# EasyEDA_Pro_Project_-_01.net
KiCad netlist of a schematic drawn in EasyEDA Pro
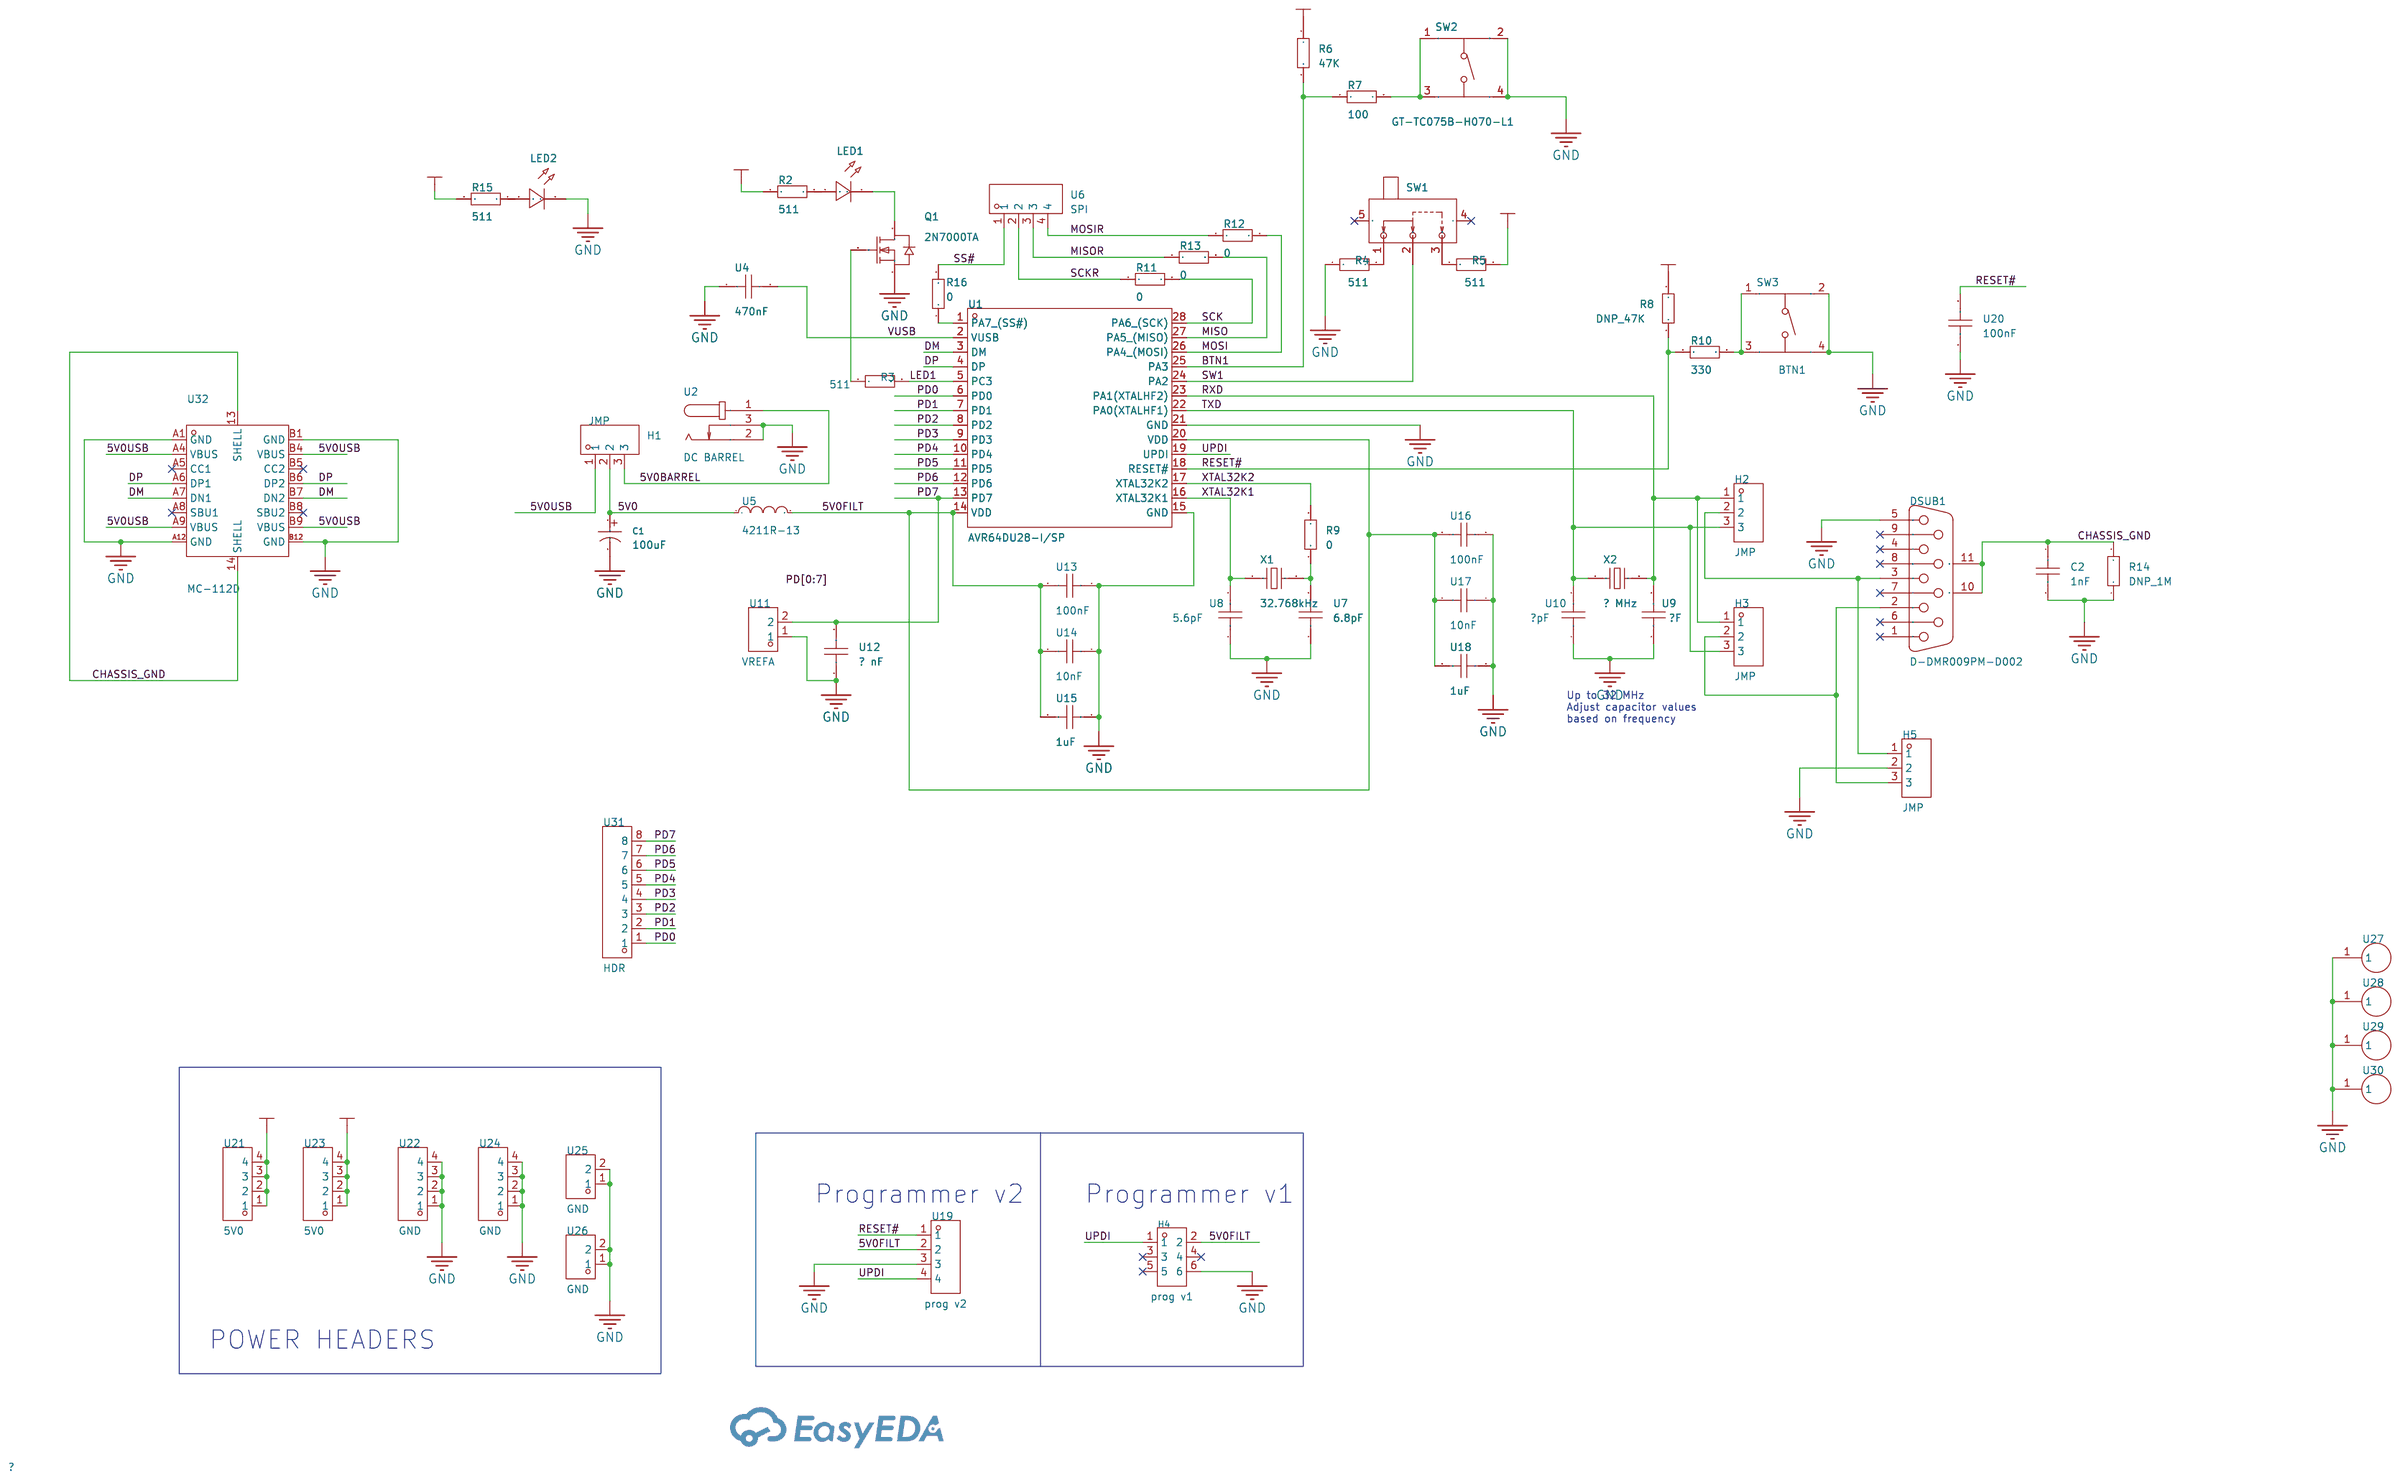
[diagram p0: schematic sheet]

(export (version "E")
  (design (tool "Eeschema 10.0.6"))
  (components
    (comp (ref "C1")
      (value "100uF")
      (footprint "easyedapro:CAP-TH_BD5.0-P2.00-D0.8-FD")
      (fields
        (field (name "Manufacturer Part") "KS107M010D07RR0VH2FP0")
        (field (name "Manufacturer") "CX(承兴)")
      )
      (libsource (lib "easyedapro") (part "100uF 10V 5*7"))
    )
    (comp (ref "C2")
      (value "1nF")
      (footprint "easyedapro:CAP-TH_L6.0-W3.5-P7.50-D1.0")
      (fields (field (name "Manufacturer Part") "Y25E1E102M") (field (name "Manufacturer") "HEL(鸿志)"))
      (libsource (lib "easyedapro") (part "Y25E1E102M"))
    )
    (comp (ref "DSUB1")
      (value "D-DMR009PM-D002")
      (footprint "easyedapro:DSUB-TH_DMR-9P")
      (fields (field (name "Manufacturer") "Ckmtw(灿科盟)"))
      (libsource (lib "easyedapro") (part "DMR-9P"))
    )
    (comp (ref "H1")
      (value "JMP")
      (footprint "easyedapro:HDR-TH_3P-P2.54-V-M-1")
      (fields (field (name "Manufacturer") "JILN(锦凌)"))
      (libsource (lib "easyedapro") (part "12251103CNG0S115001"))
    )
    (comp (ref "H2")
      (value "JMP")
      (footprint "easyedapro:HDR-TH_3P-P2.54-V-M-1")
      (fields (field (name "Manufacturer") "JILN(锦凌)"))
      (libsource (lib "easyedapro") (part "12251103CNG0S115001"))
    )
    (comp (ref "H3")
      (value "JMP")
      (footprint "easyedapro:HDR-TH_3P-P2.54-V-M-1")
      (fields (field (name "Manufacturer") "JILN(锦凌)"))
      (libsource (lib "easyedapro") (part "12251103CNG0S115001"))
    )
    (comp (ref "H4")
      (value "prog v1")
      (footprint "easyedapro:HDR-TH_6P-P2.54-V-M-R2-C3-S2.54")
      (fields (field (name "Manufacturer") "Liansheng(连盛)"))
      (libsource (lib "easyedapro") (part "PH-01291"))
    )
    (comp (ref "H5")
      (value "JMP")
      (footprint "easyedapro:HDR-TH_3P-P2.54-V-M-1")
      (fields (field (name "Manufacturer") "JILN(锦凌)"))
      (libsource (lib "easyedapro") (part "12251103CNG0S115001"))
    )
    (comp (ref "LED1")
      (value "~")
      (footprint "easyedapro:LED-TH_BD3.0-P2.54-FD")
      (libsource (lib "easyedapro") (part "LED_TH-R"))
    )
    (comp (ref "LED2")
      (value "~")
      (footprint "easyedapro:LED-TH_BD3.0-P2.54-FD")
      (libsource (lib "easyedapro") (part "LED_TH-R"))
    )
    (comp (ref "Q1")
      (value "2N7000TA")
      (footprint "easyedapro:TO-92-3_L4.8-W3.7-P2.54-L")
      (fields (field (name "Manufacturer") "onsemi(安森美)"))
      (libsource (lib "easyedapro") (part "2N7000TA"))
    )
    (comp (ref "R2")
      (value "511")
      (footprint "easyedapro:RES-TH_BD1.8-L3.2-P7.20-D0.4")
      (libsource (lib "easyedapro") (part "Res"))
    )
    (comp (ref "R3")
      (value "511")
      (footprint "easyedapro:RES-TH_BD1.8-L3.2-P7.20-D0.4")
      (libsource (lib "easyedapro") (part "Res"))
    )
    (comp (ref "R4")
      (value "511")
      (footprint "easyedapro:RES-TH_BD1.8-L3.2-P7.20-D0.4")
      (libsource (lib "easyedapro") (part "Res"))
    )
    (comp (ref "R5")
      (value "511")
      (footprint "easyedapro:RES-TH_BD1.8-L3.2-P7.20-D0.4")
      (libsource (lib "easyedapro") (part "Res"))
    )
    (comp (ref "R6")
      (value "47K")
      (footprint "easyedapro:RES-TH_BD1.8-L3.2-P7.20-D0.4")
      (libsource (lib "easyedapro") (part "Res"))
    )
    (comp (ref "R7")
      (value "100")
      (footprint "easyedapro:RES-TH_BD1.8-L3.2-P7.20-D0.4")
      (libsource (lib "easyedapro") (part "Res"))
    )
    (comp (ref "R8")
      (value "DNP_47K")
      (footprint "easyedapro:RES-TH_BD1.8-L3.2-P7.20-D0.4")
      (libsource (lib "easyedapro") (part "Res"))
    )
    (comp (ref "R9")
      (value "0")
      (footprint "easyedapro:RES-TH_BD1.8-L3.2-P7.20-D0.4")
      (libsource (lib "easyedapro") (part "Res"))
    )
    (comp (ref "R10")
      (value "330")
      (footprint "easyedapro:RES-TH_BD1.8-L3.2-P7.20-D0.4")
      (libsource (lib "easyedapro") (part "Res"))
    )
    (comp (ref "R11")
      (value "0")
      (footprint "easyedapro:RES-TH_BD1.8-L3.2-P7.20-D0.4")
      (libsource (lib "easyedapro") (part "Res"))
    )
    (comp (ref "R12")
      (value "0")
      (footprint "easyedapro:RES-TH_BD1.8-L3.2-P7.20-D0.4")
      (libsource (lib "easyedapro") (part "Res"))
    )
    (comp (ref "R13")
      (value "0")
      (footprint "easyedapro:RES-TH_BD1.8-L3.2-P7.20-D0.4")
      (libsource (lib "easyedapro") (part "Res"))
    )
    (comp (ref "R14")
      (value "DNP_1M")
      (footprint "easyedapro:RES-TH_BD1.8-L3.2-P7.20-D0.4")
      (libsource (lib "easyedapro") (part "Res"))
    )
    (comp (ref "R15")
      (value "511")
      (footprint "easyedapro:RES-TH_BD1.8-L3.2-P7.20-D0.4")
      (libsource (lib "easyedapro") (part "Res"))
    )
    (comp (ref "R16")
      (value "0")
      (footprint "easyedapro:RES-TH_BD1.8-L3.2-P7.20-D0.4")
      (libsource (lib "easyedapro") (part "Res"))
    )
    (comp (ref "SW1")
      (value "SS-12D07G4")
      (footprint "easyedapro:SW-TH_DEALON_SS-12D02-VGX")
      (fields (field (name "Manufacturer") "HanElectricity(瀚源)"))
      (libsource (lib "easyedapro") (part "SS-12D07G4"))
    )
    (comp (ref "SW2")
      (value "GT-TC075B-H070-L1")
      (footprint "easyedapro:KEY-TH_4P-L4.5-W4.5-P3.00-LS5.8")
      (fields (field (name "Manufacturer") "G-Switch(品赞)"))
      (libsource (lib "easyedapro") (part "GT-TC075B-H070-L1"))
    )
    (comp (ref "SW3")
      (value "BTN1")
      (footprint "easyedapro:KEY-TH_4P-L4.5-W4.5-P3.00-LS5.8")
      (fields (field (name "Manufacturer") "G-Switch(品赞)"))
      (libsource (lib "easyedapro") (part "GT-TC075B-H070-L1"))
    )
    (comp (ref "U1")
      (value "AVR64DU28-I/SP")
      (footprint "easyedapro:SPDIP-28_L34.7-W7.2-P2.54-LS7.9-BL")
      (fields (field (name "Manufacturer") "MICROCHIP(美国微芯)"))
      (libsource (lib "easyedapro") (part "AVR64DB28-I/SP"))
    )
    (comp (ref "U2")
      (value "DC BARREL")
      (footprint "easyedapro:DC-IN-TH_DC-005-2.0_C22459640")
      (fields (field (name "Manufacturer") "HanElectricity(瀚源)"))
      (libsource (lib "easyedapro") (part "DC-005-2.0_C22459640"))
    )
    (comp (ref "U4")
      (value "470nF")
      (footprint "easyedapro:CAP-TH_L4.8-W2.4-P5.08-D0.6")
      (fields (field (name "Manufacturer Part") "178MU0009") (field (name "Manufacturer") "KNSCHA(科尼盛)"))
      (libsource (lib "easyedapro") (part "178MU0009"))
    )
    (comp (ref "U5")
      (value "4211R-13")
      (footprint "easyedapro:IND-TH_BD3.5-L4.4_4211R-13")
      (description "Impedance @ Frequency:50Ω@100MHz Circuits:1")
      (fields (field (name "Manufacturer") "API Delevan"))
      (libsource (lib "easyedapro") (part "4211R-13"))
    )
    (comp (ref "U6")
      (value "SPI")
      (footprint "easyedapro:HDR-TH_4P-P2.00-V-M")
      (fields (field (name "Manufacturer") "Yxcon(宇熙精密)"))
      (libsource (lib "easyedapro") (part "P220-1104A0BS087A1"))
    )
    (comp (ref "U7")
      (value "6.8pF")
      (footprint "easyedapro:CAP-TH_L4.8-W2.4-P5.08-D0.6")
      (fields (field (name "Manufacturer Part") "178MU0009") (field (name "Manufacturer") "KNSCHA(科尼盛)"))
      (libsource (lib "easyedapro") (part "178MU0009"))
    )
    (comp (ref "U8")
      (value "5.6pF")
      (footprint "easyedapro:CAP-TH_L4.8-W2.4-P5.08-D0.6")
      (fields (field (name "Manufacturer Part") "178MU0009") (field (name "Manufacturer") "KNSCHA(科尼盛)"))
      (libsource (lib "easyedapro") (part "178MU0009"))
    )
    (comp (ref "U9")
      (value "?F")
      (footprint "easyedapro:CAP-TH_L4.8-W2.4-P5.08-D0.6")
      (fields (field (name "Manufacturer Part") "178MU0009") (field (name "Manufacturer") "KNSCHA(科尼盛)"))
      (libsource (lib "easyedapro") (part "178MU0009"))
    )
    (comp (ref "U10")
      (value "?pF")
      (footprint "easyedapro:CAP-TH_L4.8-W2.4-P5.08-D0.6")
      (fields (field (name "Manufacturer Part") "178MU0009") (field (name "Manufacturer") "KNSCHA(科尼盛)"))
      (libsource (lib "easyedapro") (part "178MU0009"))
    )
    (comp (ref "U11")
      (value "VREFA")
      (footprint "easyedapro:HDR-TH_2P-P2.00-V-M")
      (fields (field (name "Manufacturer") "hanxia(韩下)"))
      (libsource (lib "easyedapro") (part "HX PZ2.0-1X2P ZZ"))
    )
    (comp (ref "U12")
      (value "? nF")
      (footprint "easyedapro:CAP-TH_L4.8-W2.4-P5.08-D0.6")
      (fields (field (name "Manufacturer Part") "178MU0009") (field (name "Manufacturer") "KNSCHA(科尼盛)"))
      (libsource (lib "easyedapro") (part "178MU0009"))
    )
    (comp (ref "U13")
      (value "100nF")
      (footprint "easyedapro:CAP-TH_L4.8-W2.4-P5.08-D0.6")
      (fields (field (name "Manufacturer Part") "178MU0009") (field (name "Manufacturer") "KNSCHA(科尼盛)"))
      (libsource (lib "easyedapro") (part "178MU0009"))
    )
    (comp (ref "U14")
      (value "10nF")
      (footprint "easyedapro:CAP-TH_L4.8-W2.4-P5.08-D0.6")
      (fields (field (name "Manufacturer Part") "178MU0009") (field (name "Manufacturer") "KNSCHA(科尼盛)"))
      (libsource (lib "easyedapro") (part "178MU0009"))
    )
    (comp (ref "U15")
      (value "1uF")
      (footprint "easyedapro:CAP-TH_L4.8-W2.4-P5.08-D0.6")
      (fields (field (name "Manufacturer Part") "178MU0009") (field (name "Manufacturer") "KNSCHA(科尼盛)"))
      (libsource (lib "easyedapro") (part "178MU0009"))
    )
    (comp (ref "U16")
      (value "100nF")
      (footprint "easyedapro:CAP-TH_L4.8-W2.4-P5.08-D0.6")
      (fields (field (name "Manufacturer Part") "178MU0009") (field (name "Manufacturer") "KNSCHA(科尼盛)"))
      (libsource (lib "easyedapro") (part "178MU0009"))
    )
    (comp (ref "U17")
      (value "10nF")
      (footprint "easyedapro:CAP-TH_L4.8-W2.4-P5.08-D0.6")
      (fields (field (name "Manufacturer Part") "178MU0009") (field (name "Manufacturer") "KNSCHA(科尼盛)"))
      (libsource (lib "easyedapro") (part "178MU0009"))
    )
    (comp (ref "U18")
      (value "1uF")
      (footprint "easyedapro:CAP-TH_L4.8-W2.4-P5.08-D0.6")
      (fields (field (name "Manufacturer Part") "178MU0009") (field (name "Manufacturer") "KNSCHA(科尼盛)"))
      (libsource (lib "easyedapro") (part "178MU0009"))
    )
    (comp (ref "U19")
      (value "prog v2")
      (footprint "easyedapro:HDR-TH_4P-P2.00-V-M")
      (fields (field (name "Manufacturer") "Yxcon(宇熙精密)"))
      (libsource (lib "easyedapro") (part "P220-1104A0BS087A1"))
    )
    (comp (ref "U20")
      (value "100nF")
      (footprint "easyedapro:CAP-TH_L4.8-W2.4-P5.08-D0.6")
      (fields (field (name "Manufacturer Part") "178MU0009") (field (name "Manufacturer") "KNSCHA(科尼盛)"))
      (libsource (lib "easyedapro") (part "178MU0009"))
    )
    (comp (ref "U21")
      (value "5V0")
      (footprint "easyedapro:HDR-TH_4P-P2.00-V-M")
      (fields (field (name "Manufacturer") "Yxcon(宇熙精密)"))
      (libsource (lib "easyedapro") (part "P220-1104A0BS087A1"))
    )
    (comp (ref "U22")
      (value "GND")
      (footprint "easyedapro:HDR-TH_4P-P2.00-V-M")
      (fields (field (name "Manufacturer") "Yxcon(宇熙精密)"))
      (libsource (lib "easyedapro") (part "P220-1104A0BS087A1"))
    )
    (comp (ref "U23")
      (value "5V0")
      (footprint "easyedapro:HDR-TH_4P-P2.00-V-M")
      (fields (field (name "Manufacturer") "Yxcon(宇熙精密)"))
      (libsource (lib "easyedapro") (part "P220-1104A0BS087A1"))
    )
    (comp (ref "U24")
      (value "GND")
      (footprint "easyedapro:HDR-TH_4P-P2.00-V-M")
      (fields (field (name "Manufacturer") "Yxcon(宇熙精密)"))
      (libsource (lib "easyedapro") (part "P220-1104A0BS087A1"))
    )
    (comp (ref "U25")
      (value "GND")
      (footprint "easyedapro:HDR-TH_2P-P2.00-V-M")
      (fields (field (name "Manufacturer") "hanxia(韩下)"))
      (libsource (lib "easyedapro") (part "HX PZ2.0-1X2P ZZ"))
    )
    (comp (ref "U26")
      (value "GND")
      (footprint "easyedapro:HDR-TH_2P-P2.00-V-M")
      (fields (field (name "Manufacturer") "hanxia(韩下)"))
      (libsource (lib "easyedapro") (part "HX PZ2.0-1X2P ZZ"))
    )
    (comp (ref "U27")
      (value "~")
      (footprint "easyedapro:Standoff 2.0mm")
      (libsource (lib "easyedapro") (part "Standoff 2.0mm"))
    )
    (comp (ref "U28")
      (value "~")
      (footprint "easyedapro:Standoff 2.0mm")
      (libsource (lib "easyedapro") (part "Standoff 2.0mm"))
    )
    (comp (ref "U29")
      (value "~")
      (footprint "easyedapro:Standoff 2.0mm")
      (libsource (lib "easyedapro") (part "Standoff 2.0mm"))
    )
    (comp (ref "U30")
      (value "~")
      (footprint "easyedapro:Standoff 2.0mm")
      (libsource (lib "easyedapro") (part "Standoff 2.0mm"))
    )
    (comp (ref "U31")
      (value "HDR")
      (footprint "easyedapro:HDR-TH_8P-P2.54-V-M")
      (fields (field (name "Manufacturer") "HANBO(汉博)"))
      (libsource (lib "easyedapro") (part "HB-PH3-25418PB2GOP"))
    )
    (comp (ref "U32")
      (value "MC-112D")
      (footprint "easyedapro:USB-C-TH_HANBO_MC-112D")
      (fields (field (name "Manufacturer") "HANBO(汉博)"))
      (libsource (lib "easyedapro") (part "MC-112D"))
    )
    (comp (ref "X1")
      (value "32.768kHz")
      (footprint "easyedapro:OSC-TH_BD2.0-P0.70-D0.3")
      (fields
        (field (name "Manufacturer Part") "TAXD32768K2BGBBZT2S")
        (field (name "Manufacturer") "YJX(雅晶鑫)")
      )
      (libsource (lib "easyedapro") (part "TAXD32768K2BGBBZT2S"))
    )
    (comp (ref "X2")
      (value "? MHz")
      (footprint "easyedapro:OSC-TH_BD2.0-P0.70-D0.3")
      (fields
        (field (name "Manufacturer Part") "TAXD32768K2BGBBZT2S")
        (field (name "Manufacturer") "YJX(雅晶鑫)")
      )
      (libsource (lib "easyedapro") (part "TAXD32768K2BGBBZT2S"))
    )
  )
  (nets
    (net (code "1") (name "/5V0BARREL") (class "Default")
      (node (ref "H1") (pin "3") (pinfunction "3_3") (pintype "unspecified"))
      (node (ref "U2") (pin "1") (pinfunction "1_1") (pintype "unspecified"))
    )
    (net (code "2") (name "/5V0FILT") (class "Default")
      (node (ref "H4") (pin "2") (pinfunction "2_2") (pintype "input"))
      (node (ref "U1") (pin "14") (pinfunction "VDD_14") (pintype "unspecified"))
      (node (ref "U1") (pin "20") (pinfunction "VDD_20") (pintype "unspecified"))
      (node (ref "U13") (pin "2") (pinfunction "2_2") (pintype "unspecified"))
      (node (ref "U14") (pin "2") (pinfunction "2_2") (pintype "unspecified"))
      (node (ref "U15") (pin "2") (pinfunction "2_2") (pintype "unspecified"))
      (node (ref "U16") (pin "2") (pinfunction "2_2") (pintype "unspecified"))
      (node (ref "U17") (pin "2") (pinfunction "2_2") (pintype "unspecified"))
      (node (ref "U18") (pin "2") (pinfunction "2_2") (pintype "unspecified"))
      (node (ref "U19") (pin "2") (pinfunction "2_2") (pintype "unspecified"))
      (node (ref "U5") (pin "2") (pinfunction "2_2") (pintype "unspecified"))
    )
    (net (code "3") (name "/5V0USB") (class "Default")
      (node (ref "H1") (pin "1") (pinfunction "1_1") (pintype "unspecified"))
      (node (ref "U32") (pin "A4") (pinfunction "VBUS_A4") (pintype "unspecified"))
      (node (ref "U32") (pin "A9") (pinfunction "VBUS_A9") (pintype "unspecified"))
      (node (ref "U32") (pin "B4") (pinfunction "VBUS_B4") (pintype "unspecified"))
      (node (ref "U32") (pin "B9") (pinfunction "VBUS_B9") (pintype "unspecified"))
    )
    (net (code "4") (name "/BTN1") (class "Default")
      (node (ref "R6") (pin "2") (pinfunction "2_2") (pintype "input"))
      (node (ref "R7") (pin "1") (pinfunction "1_1") (pintype "input"))
      (node (ref "U1") (pin "25") (pinfunction "PA3_25") (pintype "unspecified"))
    )
    (net (code "5") (name "/CHASSIS_GND") (class "Default")
      (node (ref "C2") (pin "1") (pinfunction "1_1") (pintype "input"))
      (node (ref "DSUB1") (pin "10") (pinfunction "MH1_10") (pintype "input"))
      (node (ref "DSUB1") (pin "11") (pinfunction "MH2_11") (pintype "input"))
      (node (ref "R14") (pin "2") (pinfunction "2_2") (pintype "input"))
      (node (ref "U32") (pin "13") (pinfunction "SHELL_13") (pintype "unspecified"))
      (node (ref "U32") (pin "14") (pinfunction "SHELL_14") (pintype "unspecified"))
    )
    (net (code "6") (name "/DM") (class "Default")
      (node (ref "U1") (pin "3") (pinfunction "DM_3") (pintype "unspecified"))
      (node (ref "U32") (pin "A7") (pinfunction "DN1_A7") (pintype "unspecified"))
      (node (ref "U32") (pin "B7") (pinfunction "DN2_B7") (pintype "unspecified"))
    )
    (net (code "7") (name "/DP") (class "Default")
      (node (ref "U1") (pin "4") (pinfunction "DP_4") (pintype "unspecified"))
      (node (ref "U32") (pin "A6") (pinfunction "DP1_A6") (pintype "unspecified"))
      (node (ref "U32") (pin "B6") (pinfunction "DP2_B6") (pintype "unspecified"))
    )
    (net (code "8") (name "/LED1") (class "Default")
      (node (ref "R3") (pin "2") (pinfunction "2_2") (pintype "input"))
      (node (ref "U1") (pin "5") (pinfunction "PC3_5") (pintype "unspecified"))
    )
    (net (code "9") (name "/MISO") (class "Default")
      (node (ref "R13") (pin "2") (pinfunction "2_2") (pintype "input"))
      (node (ref "U1") (pin "27") (pinfunction "PA5_(MISO)_27") (pintype "unspecified"))
    )
    (net (code "10") (name "/MISOR") (class "Default")
      (node (ref "R13") (pin "1") (pinfunction "1_1") (pintype "input"))
      (node (ref "U6") (pin "3") (pinfunction "3_3") (pintype "unspecified"))
    )
    (net (code "11") (name "/MOSI") (class "Default")
      (node (ref "R12") (pin "2") (pinfunction "2_2") (pintype "input"))
      (node (ref "U1") (pin "26") (pinfunction "PA4_(MOSI)_26") (pintype "unspecified"))
    )
    (net (code "12") (name "/MOSIR") (class "Default")
      (node (ref "R12") (pin "1") (pinfunction "1_1") (pintype "input"))
      (node (ref "U6") (pin "4") (pinfunction "4_4") (pintype "unspecified"))
    )
    (net (code "13") (name "/PD0") (class "Default")
      (node (ref "U1") (pin "6") (pinfunction "PD0_6") (pintype "unspecified"))
      (node (ref "U31") (pin "1") (pinfunction "1_1") (pintype "unspecified"))
    )
    (net (code "14") (name "/PD1") (class "Default")
      (node (ref "U1") (pin "7") (pinfunction "PD1_7") (pintype "unspecified"))
      (node (ref "U31") (pin "2") (pinfunction "2_2") (pintype "unspecified"))
    )
    (net (code "15") (name "/PD2") (class "Default")
      (node (ref "U1") (pin "8") (pinfunction "PD2_8") (pintype "unspecified"))
      (node (ref "U31") (pin "3") (pinfunction "3_3") (pintype "unspecified"))
    )
    (net (code "16") (name "/PD3") (class "Default")
      (node (ref "U1") (pin "9") (pinfunction "PD3_9") (pintype "unspecified"))
      (node (ref "U31") (pin "4") (pinfunction "4_4") (pintype "unspecified"))
    )
    (net (code "17") (name "/PD4") (class "Default")
      (node (ref "U1") (pin "10") (pinfunction "PD4_10") (pintype "unspecified"))
      (node (ref "U31") (pin "5") (pinfunction "5_5") (pintype "unspecified"))
    )
    (net (code "18") (name "/PD5") (class "Default")
      (node (ref "U1") (pin "11") (pinfunction "PD5_11") (pintype "unspecified"))
      (node (ref "U31") (pin "6") (pinfunction "6_6") (pintype "unspecified"))
    )
    (net (code "19") (name "/PD6") (class "Default")
      (node (ref "U1") (pin "12") (pinfunction "PD6_12") (pintype "unspecified"))
      (node (ref "U31") (pin "7") (pinfunction "7_7") (pintype "unspecified"))
    )
    (net (code "20") (name "/PD7") (class "Default")
      (node (ref "U1") (pin "13") (pinfunction "PD7_13") (pintype "unspecified"))
      (node (ref "U11") (pin "2") (pinfunction "2_2") (pintype "unspecified"))
      (node (ref "U12") (pin "2") (pinfunction "2_2") (pintype "unspecified"))
      (node (ref "U31") (pin "8") (pinfunction "8_8") (pintype "unspecified"))
    )
    (net (code "22") (name "/RESET#") (class "Default")
      (node (ref "R10") (pin "1") (pinfunction "1_1") (pintype "input"))
      (node (ref "R8") (pin "2") (pinfunction "2_2") (pintype "input"))
      (node (ref "U1") (pin "18") (pinfunction "RESET#_18") (pintype "unspecified"))
      (node (ref "U19") (pin "1") (pinfunction "1_1") (pintype "unspecified"))
      (node (ref "U20") (pin "2") (pinfunction "2_2") (pintype "unspecified"))
    )
    (net (code "23") (name "/RXD") (class "Default")
      (node (ref "H2") (pin "1") (pinfunction "1_1") (pintype "unspecified"))
      (node (ref "H3") (pin "1") (pinfunction "1_1") (pintype "unspecified"))
      (node (ref "U1") (pin "23") (pinfunction "PA1(XTALHF2)_23") (pintype "unspecified"))
      (node (ref "U9") (pin "2") (pinfunction "2_2") (pintype "unspecified"))
      (node (ref "X2") (pin "2") (pinfunction "2_2") (pintype "input"))
    )
    (net (code "24") (name "/SCK") (class "Default")
      (node (ref "R11") (pin "2") (pinfunction "2_2") (pintype "input"))
      (node (ref "U1") (pin "28") (pinfunction "PA6_(SCK)_28") (pintype "unspecified"))
    )
    (net (code "25") (name "/SCKR") (class "Default")
      (node (ref "R11") (pin "1") (pinfunction "1_1") (pintype "input"))
      (node (ref "U6") (pin "2") (pinfunction "2_2") (pintype "unspecified"))
    )
    (net (code "26") (name "/SS#") (class "Default")
      (node (ref "R16") (pin "2") (pinfunction "2_2") (pintype "input"))
      (node (ref "U6") (pin "1") (pinfunction "1_1") (pintype "unspecified"))
    )
    (net (code "27") (name "/SW1") (class "Default")
      (node (ref "SW1") (pin "2") (pinfunction "2_2") (pintype "unspecified"))
      (node (ref "U1") (pin "24") (pinfunction "PA2_24") (pintype "unspecified"))
    )
    (net (code "28") (name "/TXD") (class "Default")
      (node (ref "H2") (pin "3") (pinfunction "3_3") (pintype "unspecified"))
      (node (ref "H3") (pin "3") (pinfunction "3_3") (pintype "unspecified"))
      (node (ref "U1") (pin "22") (pinfunction "PA0(XTALHF1)_22") (pintype "unspecified"))
      (node (ref "U10") (pin "2") (pinfunction "2_2") (pintype "unspecified"))
      (node (ref "X2") (pin "1") (pinfunction "1_1") (pintype "input"))
    )
    (net (code "29") (name "/UPDI") (class "Default")
      (node (ref "H4") (pin "1") (pinfunction "1_1") (pintype "input"))
      (node (ref "U1") (pin "19") (pinfunction "UPDI_19") (pintype "unspecified"))
      (node (ref "U19") (pin "4") (pinfunction "4_4") (pintype "unspecified"))
    )
    (net (code "30") (name "/VUSB") (class "Default")
      (node (ref "U1") (pin "2") (pinfunction "VUSB_2") (pintype "unspecified"))
      (node (ref "U4") (pin "2") (pinfunction "2_2") (pintype "unspecified"))
    )
    (net (code "31") (name "/XTAL32K1") (class "Default")
      (node (ref "U1") (pin "16") (pinfunction "XTAL32K1_16") (pintype "unspecified"))
      (node (ref "U8") (pin "2") (pinfunction "2_2") (pintype "unspecified"))
      (node (ref "X1") (pin "1") (pinfunction "1_1") (pintype "input"))
    )
    (net (code "32") (name "/XTAL32K2") (class "Default")
      (node (ref "R9") (pin "1") (pinfunction "1_1") (pintype "input"))
      (node (ref "U1") (pin "17") (pinfunction "XTAL32K2_17") (pintype "unspecified"))
    )
    (net (code "33") (name "5V0") (class "Default")
      (node (ref "C1") (pin "1") (pinfunction "1_1") (pintype "input"))
      (node (ref "H1") (pin "2") (pinfunction "2_2") (pintype "unspecified"))
      (node (ref "R15") (pin "2") (pinfunction "2_2") (pintype "input"))
      (node (ref "R2") (pin "2") (pinfunction "2_2") (pintype "input"))
      (node (ref "R5") (pin "2") (pinfunction "2_2") (pintype "input"))
      (node (ref "R6") (pin "1") (pinfunction "1_1") (pintype "input"))
      (node (ref "R8") (pin "1") (pinfunction "1_1") (pintype "input"))
      (node (ref "U21") (pin "1") (pinfunction "1_1") (pintype "unspecified"))
      (node (ref "U21") (pin "2") (pinfunction "2_2") (pintype "unspecified"))
      (node (ref "U21") (pin "3") (pinfunction "3_3") (pintype "unspecified"))
      (node (ref "U21") (pin "4") (pinfunction "4_4") (pintype "unspecified"))
      (node (ref "U23") (pin "1") (pinfunction "1_1") (pintype "unspecified"))
      (node (ref "U23") (pin "2") (pinfunction "2_2") (pintype "unspecified"))
      (node (ref "U23") (pin "3") (pinfunction "3_3") (pintype "unspecified"))
      (node (ref "U23") (pin "4") (pinfunction "4_4") (pintype "unspecified"))
      (node (ref "U5") (pin "1") (pinfunction "1_1") (pintype "unspecified"))
    )
    (net (code "34") (name "GND") (class "Default")
      (node (ref "C1") (pin "2") (pinfunction "2_2") (pintype "input"))
      (node (ref "C2") (pin "2") (pinfunction "2_2") (pintype "input"))
      (node (ref "DSUB1") (pin "5") (pinfunction "5_5") (pintype "input"))
      (node (ref "H4") (pin "6") (pinfunction "6_6") (pintype "input"))
      (node (ref "H5") (pin "2") (pinfunction "2_2") (pintype "unspecified"))
      (node (ref "LED2") (pin "2") (pinfunction "A_2") (pintype "input"))
      (node (ref "Q1") (pin "1") (pinfunction "S_1") (pintype "unspecified"))
      (node (ref "R14") (pin "1") (pinfunction "1_1") (pintype "input"))
      (node (ref "R4") (pin "1") (pinfunction "1_1") (pintype "input"))
      (node (ref "SW2") (pin "2") (pinfunction "2_2") (pintype "unspecified"))
      (node (ref "SW2") (pin "4") (pinfunction "4_4") (pintype "unspecified"))
      (node (ref "SW3") (pin "2") (pinfunction "2_2") (pintype "unspecified"))
      (node (ref "SW3") (pin "4") (pinfunction "4_4") (pintype "unspecified"))
      (node (ref "U1") (pin "15") (pinfunction "GND_15") (pintype "unspecified"))
      (node (ref "U1") (pin "21") (pinfunction "GND_21") (pintype "unspecified"))
      (node (ref "U10") (pin "1") (pinfunction "1_1") (pintype "unspecified"))
      (node (ref "U11") (pin "1") (pinfunction "1_1") (pintype "unspecified"))
      (node (ref "U12") (pin "1") (pinfunction "1_1") (pintype "unspecified"))
      (node (ref "U13") (pin "1") (pinfunction "1_1") (pintype "unspecified"))
      (node (ref "U14") (pin "1") (pinfunction "1_1") (pintype "unspecified"))
      (node (ref "U15") (pin "1") (pinfunction "1_1") (pintype "unspecified"))
      (node (ref "U16") (pin "1") (pinfunction "1_1") (pintype "unspecified"))
      (node (ref "U17") (pin "1") (pinfunction "1_1") (pintype "unspecified"))
      (node (ref "U18") (pin "1") (pinfunction "1_1") (pintype "unspecified"))
      (node (ref "U19") (pin "3") (pinfunction "3_3") (pintype "unspecified"))
      (node (ref "U2") (pin "2") (pinfunction "2_2") (pintype "unspecified"))
      (node (ref "U2") (pin "3") (pinfunction "3_3") (pintype "unspecified"))
      (node (ref "U20") (pin "1") (pinfunction "1_1") (pintype "unspecified"))
      (node (ref "U22") (pin "1") (pinfunction "1_1") (pintype "unspecified"))
      (node (ref "U22") (pin "2") (pinfunction "2_2") (pintype "unspecified"))
      (node (ref "U22") (pin "3") (pinfunction "3_3") (pintype "unspecified"))
      (node (ref "U22") (pin "4") (pinfunction "4_4") (pintype "unspecified"))
      (node (ref "U24") (pin "1") (pinfunction "1_1") (pintype "unspecified"))
      (node (ref "U24") (pin "2") (pinfunction "2_2") (pintype "unspecified"))
      (node (ref "U24") (pin "3") (pinfunction "3_3") (pintype "unspecified"))
      (node (ref "U24") (pin "4") (pinfunction "4_4") (pintype "unspecified"))
      (node (ref "U25") (pin "1") (pinfunction "1_1") (pintype "unspecified"))
      (node (ref "U25") (pin "2") (pinfunction "2_2") (pintype "unspecified"))
      (node (ref "U26") (pin "1") (pinfunction "1_1") (pintype "unspecified"))
      (node (ref "U26") (pin "2") (pinfunction "2_2") (pintype "unspecified"))
      (node (ref "U27") (pin "1") (pinfunction "1_1") (pintype "input"))
      (node (ref "U28") (pin "1") (pinfunction "1_1") (pintype "input"))
      (node (ref "U29") (pin "1") (pinfunction "1_1") (pintype "input"))
      (node (ref "U30") (pin "1") (pinfunction "1_1") (pintype "input"))
      (node (ref "U32") (pin "A1") (pinfunction "GND_A1") (pintype "unspecified"))
      (node (ref "U32") (pin "A12") (pinfunction "GND_A12") (pintype "unspecified"))
      (node (ref "U32") (pin "B1") (pinfunction "GND_B1") (pintype "unspecified"))
      (node (ref "U32") (pin "B12") (pinfunction "GND_B12") (pintype "unspecified"))
      (node (ref "U4") (pin "1") (pinfunction "1_1") (pintype "unspecified"))
      (node (ref "U7") (pin "1") (pinfunction "1_1") (pintype "unspecified"))
      (node (ref "U8") (pin "1") (pinfunction "1_1") (pintype "unspecified"))
      (node (ref "U9") (pin "1") (pinfunction "1_1") (pintype "unspecified"))
    )
    (net (code "35") (name "Net-(DSUB1-Pad2)") (class "Default")
      (node (ref "DSUB1") (pin "2") (pinfunction "2_2") (pintype "input"))
      (node (ref "H3") (pin "2") (pinfunction "2_2") (pintype "unspecified"))
      (node (ref "H5") (pin "3") (pinfunction "3_3") (pintype "unspecified"))
    )
    (net (code "36") (name "Net-(DSUB1-Pad3)") (class "Default")
      (node (ref "DSUB1") (pin "3") (pinfunction "3_3") (pintype "input"))
      (node (ref "H2") (pin "2") (pinfunction "2_2") (pintype "unspecified"))
      (node (ref "H5") (pin "1") (pinfunction "1_1") (pintype "unspecified"))
    )
    (net (code "37") (name "Net-(LED1-A)") (class "Default")
      (node (ref "LED1") (pin "2") (pinfunction "A_2") (pintype "input"))
      (node (ref "Q1") (pin "3") (pinfunction "D_3") (pintype "unspecified"))
    )
    (net (code "38") (name "Net-(LED1-C)") (class "Default")
      (node (ref "LED1") (pin "1") (pinfunction "C_1") (pintype "input"))
      (node (ref "R2") (pin "1") (pinfunction "1_1") (pintype "input"))
    )
    (net (code "39") (name "Net-(LED2-C)") (class "Default")
      (node (ref "LED2") (pin "1") (pinfunction "C_1") (pintype "input"))
      (node (ref "R15") (pin "1") (pinfunction "1_1") (pintype "input"))
    )
    (net (code "40") (name "Net-(Q1-G)") (class "Default")
      (node (ref "Q1") (pin "2") (pinfunction "G_2") (pintype "unspecified"))
      (node (ref "R3") (pin "1") (pinfunction "1_1") (pintype "input"))
    )
    (net (code "41") (name "Net-(R4-Pad2)") (class "Default")
      (node (ref "R4") (pin "2") (pinfunction "2_2") (pintype "input"))
      (node (ref "SW1") (pin "1") (pinfunction "1_1") (pintype "unspecified"))
    )
    (net (code "42") (name "Net-(R5-Pad1)") (class "Default")
      (node (ref "R5") (pin "1") (pinfunction "1_1") (pintype "input"))
      (node (ref "SW1") (pin "3") (pinfunction "3_3") (pintype "unspecified"))
    )
    (net (code "43") (name "Net-(R7-Pad2)") (class "Default")
      (node (ref "R7") (pin "2") (pinfunction "2_2") (pintype "input"))
      (node (ref "SW2") (pin "1") (pinfunction "1_1") (pintype "unspecified"))
      (node (ref "SW2") (pin "3") (pinfunction "3_3") (pintype "unspecified"))
    )
    (net (code "44") (name "Net-(R9-Pad2)") (class "Default")
      (node (ref "R9") (pin "2") (pinfunction "2_2") (pintype "input"))
      (node (ref "U7") (pin "2") (pinfunction "2_2") (pintype "unspecified"))
      (node (ref "X1") (pin "2") (pinfunction "2_2") (pintype "input"))
    )
    (net (code "45") (name "Net-(R10-Pad2)") (class "Default")
      (node (ref "R10") (pin "2") (pinfunction "2_2") (pintype "input"))
      (node (ref "SW3") (pin "1") (pinfunction "1_1") (pintype "unspecified"))
      (node (ref "SW3") (pin "3") (pinfunction "3_3") (pintype "unspecified"))
    )
    (net (code "46") (name "Net-(U1-PA7_(SS#))") (class "Default")
      (node (ref "R16") (pin "1") (pinfunction "1_1") (pintype "input"))
      (node (ref "U1") (pin "1") (pinfunction "PA7_(SS#)_1") (pintype "unspecified"))
    )
    (net (code "47") (name "unconnected-(DSUB1-Pad1)") (class "Default")
      (node (ref "DSUB1") (pin "1") (pinfunction "1_1") (pintype "input+no_connect"))
    )
    (net (code "48") (name "unconnected-(DSUB1-Pad4)") (class "Default")
      (node (ref "DSUB1") (pin "4") (pinfunction "4_4") (pintype "input+no_connect"))
    )
    (net (code "49") (name "unconnected-(DSUB1-Pad6)") (class "Default")
      (node (ref "DSUB1") (pin "6") (pinfunction "6_6") (pintype "input+no_connect"))
    )
    (net (code "50") (name "unconnected-(DSUB1-Pad7)") (class "Default")
      (node (ref "DSUB1") (pin "7") (pinfunction "7_7") (pintype "input+no_connect"))
    )
    (net (code "51") (name "unconnected-(DSUB1-Pad8)") (class "Default")
      (node (ref "DSUB1") (pin "8") (pinfunction "8_8") (pintype "input+no_connect"))
    )
    (net (code "52") (name "unconnected-(DSUB1-Pad9)") (class "Default")
      (node (ref "DSUB1") (pin "9") (pinfunction "9_9") (pintype "input+no_connect"))
    )
    (net (code "53") (name "unconnected-(H4-Pad3)") (class "Default")
      (node (ref "H4") (pin "3") (pinfunction "3_3") (pintype "input+no_connect"))
    )
    (net (code "54") (name "unconnected-(H4-Pad4)") (class "Default")
      (node (ref "H4") (pin "4") (pinfunction "4_4") (pintype "input+no_connect"))
    )
    (net (code "55") (name "unconnected-(H4-Pad5)") (class "Default")
      (node (ref "H4") (pin "5") (pinfunction "5_5") (pintype "input+no_connect"))
    )
    (net (code "56") (name "unconnected-(SW1-Pad4)") (class "Default")
      (node (ref "SW1") (pin "4") (pinfunction "4_4") (pintype "unspecified+no_connect"))
    )
    (net (code "57") (name "unconnected-(SW1-Pad5)") (class "Default")
      (node (ref "SW1") (pin "5") (pinfunction "5_5") (pintype "unspecified+no_connect"))
    )
    (net (code "58") (name "unconnected-(U32-CC1-PadA5)") (class "Default")
      (node (ref "U32") (pin "A5") (pinfunction "CC1_A5") (pintype "unspecified+no_connect"))
    )
    (net (code "59") (name "unconnected-(U32-CC2-PadB5)") (class "Default")
      (node (ref "U32") (pin "B5") (pinfunction "CC2_B5") (pintype "unspecified+no_connect"))
    )
    (net (code "60") (name "unconnected-(U32-SBU1-PadA8)") (class "Default")
      (node (ref "U32") (pin "A8") (pinfunction "SBU1_A8") (pintype "unspecified+no_connect"))
    )
    (net (code "61") (name "unconnected-(U32-SBU2-PadB8)") (class "Default")
      (node (ref "U32") (pin "B8") (pinfunction "SBU2_B8") (pintype "unspecified+no_connect"))
    )
  )
)
